# WE_1100_top.net
KiCad netlist of a schematic drawn in Altium Designer
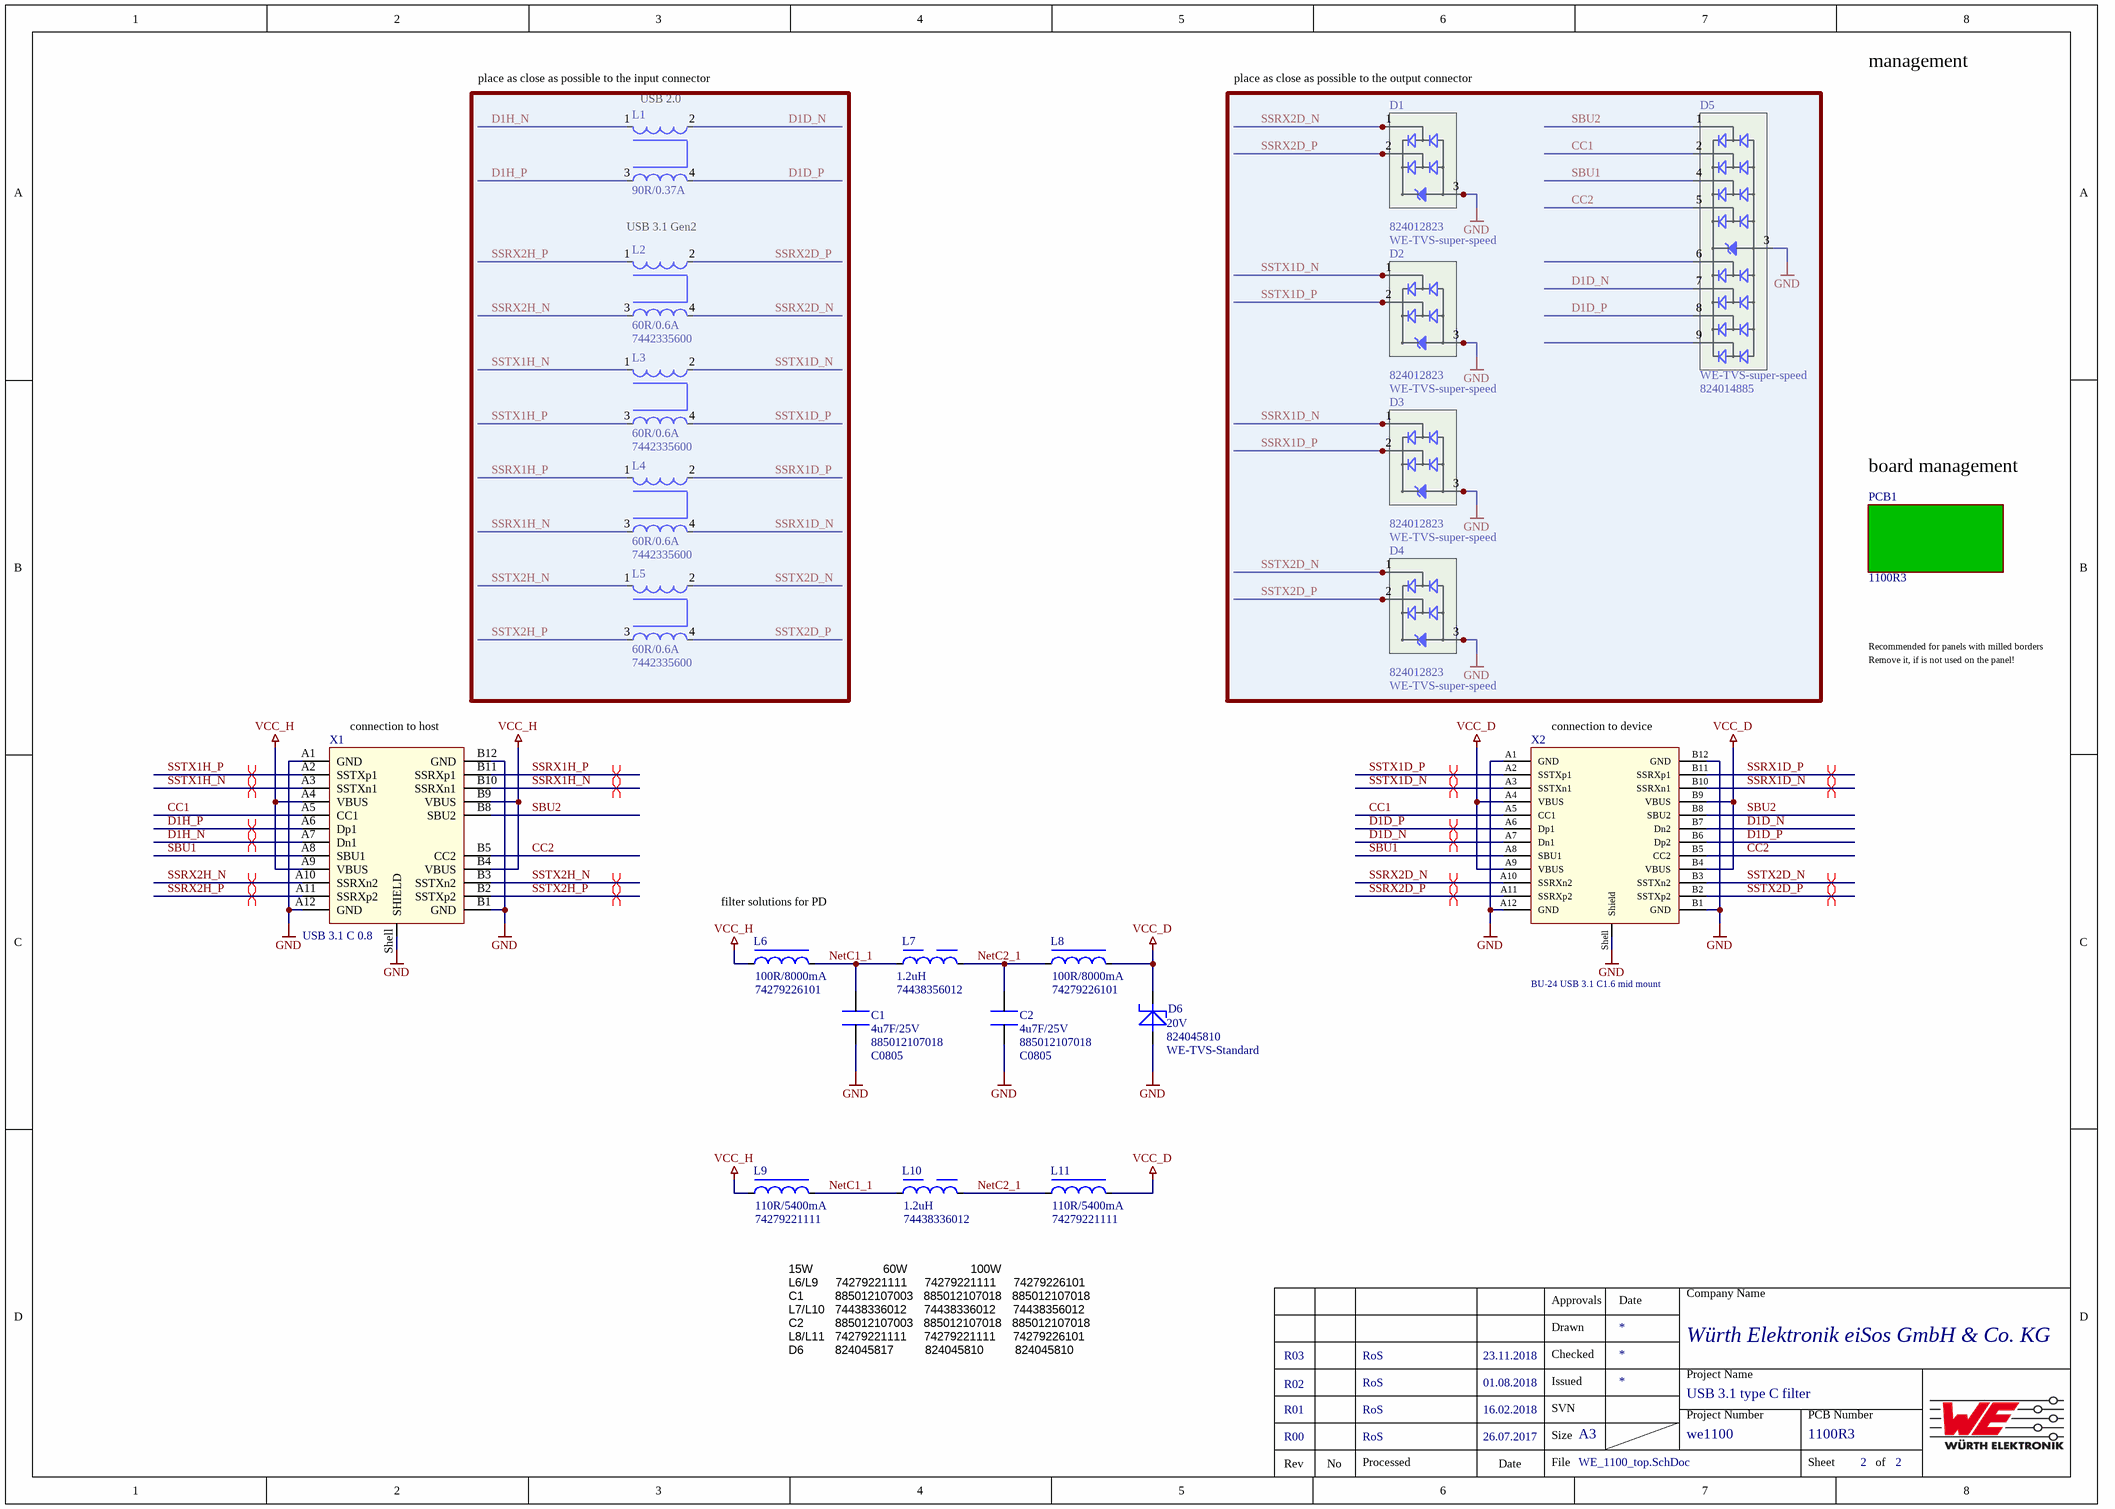
[diagram p0: WE_1100_top.SchDoc]

(export (version "E")
  (design (tool "Eeschema 10.0.6"))
  (components
    (comp (ref "C1")
      (value "4u7F/25V")
      (footprint "C0805 (reflow)")
      (description "Ceramic SMT X5R 4,7uF/25V 0805")
      (fields
        (field (name "ART.-CODE") "885012107018")
        (field (name "MANUFACTURER") "WE")
        (field (name "TOLERANCE") "20%")
        (field (name "CASE") "C0805")
      )
      (libsource (lib "capacitor") (part "4UF7/25-X5R-0805"))
    )
    (comp (ref "C2")
      (value "4u7F/25V")
      (footprint "C0805 (reflow)")
      (description "Ceramic SMT X5R 4,7uF/25V 0805")
      (fields
        (field (name "ART.-CODE") "885012107018")
        (field (name "MANUFACTURER") "WE")
        (field (name "TOLERANCE") "20%")
        (field (name "CASE") "C0805")
      )
      (libsource (lib "capacitor") (part "4UF7/25-X5R-0805"))
    )
    (comp (ref "D1")
      (value "WE-TVS-super-speed")
      (footprint "DFN88P100X50-6L")
      (description "TVS, diode, array, 2 channel ESD protection, 3.3V, DFN1012-6")
      (fields
        (field (name "MANUFACTURER") "WE")
        (field (name "VOLTAGE") "3.3V")
        (field (name "PART-NO.") "824012823")
      )
      (libsource (lib "rectifier") (part "WE-TVS-ULC-DFN1012-6"))
    )
    (comp (ref "D2")
      (value "WE-TVS-super-speed")
      (footprint "DFN88P100X50-6L")
      (description "TVS, diode, array, 2 channel ESD protection, 3.3V, DFN1012-6")
      (fields
        (field (name "MANUFACTURER") "WE")
        (field (name "VOLTAGE") "3.3V")
        (field (name "PART-NO.") "824012823")
      )
      (libsource (lib "rectifier") (part "WE-TVS-ULC-DFN1012-6"))
    )
    (comp (ref "D3")
      (value "WE-TVS-super-speed")
      (footprint "DFN88P100X50-6L")
      (description "TVS, diode, array, 2 channel ESD protection, 3.3V, DFN1012-6")
      (fields
        (field (name "MANUFACTURER") "WE")
        (field (name "VOLTAGE") "3.3V")
        (field (name "PART-NO.") "824012823")
      )
      (libsource (lib "rectifier") (part "WE-TVS-ULC-DFN1012-6"))
    )
    (comp (ref "D4")
      (value "WE-TVS-super-speed")
      (footprint "DFN88P100X50-6L")
      (description "TVS, diode, array, 2 channel ESD protection, 3.3V, DFN1012-6")
      (fields
        (field (name "MANUFACTURER") "WE")
        (field (name "VOLTAGE") "3.3V")
        (field (name "PART-NO.") "824012823")
      )
      (libsource (lib "rectifier") (part "WE-TVS-ULC-DFN1012-6"))
    )
    (comp (ref "D5")
      (value "WE-TVS-super-speed")
      (footprint "DFN90P380X55-9L")
      (description "TVS, diode, array, 8 channel ESD protection, 1.2V, DFN3810-9")
      (fields
        (field (name "MANUFACTURER") "WE")
        (field (name "VOLTAGE") "1.2V")
        (field (name "PART-NO.") "824014885")
      )
      (libsource (lib "rectifier") (part "WE-TVS-ULC-DFN3810"))
    )
    (comp (ref "D6")
      (value "WE-TVS-Standard")
      (footprint "DFN110P160X55-2L")
      (description "TVS, diode, unidir, ESD protection, 20V, DFN1610")
      (fields
        (field (name "MANUFACTURER") "WE")
        (field (name "VOLTAGE") "20V")
        (field (name "PART-NO.") "824045810")
      )
      (libsource (lib "rectifier") (part "WE-TVS20-ULC-DFN1610"))
    )
    (comp (ref "L1")
      (value "90R/0.37A")
      (footprint "WE-CNSW-0805 (REFLOW)")
      (description "Common mode line filter SMD WE-CNSW (USB, LVDS)")
      (fields
        (field (name "MANUFACTURER") "WE")
        (field (name "TOLERANCE") "25%")
        (field (name "HELPURL") "d:\\Hardware\\Datasheet\\Induktivitäten\\WE-CNSW\\744231091.pdf")
      )
      (libsource (lib "inductance") (part "Z90R-370mA-WE-CNSW"))
    )
    (comp (ref "L2")
      (value "60R/0.6A")
      (footprint "WE-CNSW-HF-0504 (REFLOW)")
      (description "Common mode line filter SMD WE-CNSW HF (USB3.0)")
      (fields
        (field (name "MANUFACTURER") "WE")
        (field (name "TOLERANCE") "25%")
        (field (name "PART-NO.") "7442335600")
        (field (name "HELPURL") "d:\\Hardware\\Datasheet\\Induktivitäten\\WE-CNSW_HF\\7442335600.pdf")
      )
      (libsource (lib "inductance") (part "Z60R-600mA-WE-CNSW HF"))
    )
    (comp (ref "L3")
      (value "60R/0.6A")
      (footprint "WE-CNSW-HF-0504 (REFLOW)")
      (description "Common mode line filter SMD WE-CNSW HF (USB3.0)")
      (fields
        (field (name "MANUFACTURER") "WE")
        (field (name "TOLERANCE") "25%")
        (field (name "PART-NO.") "7442335600")
        (field (name "HELPURL") "d:\\Hardware\\Datasheet\\Induktivitäten\\WE-CNSW_HF\\7442335600.pdf")
      )
      (libsource (lib "inductance") (part "Z60R-600mA-WE-CNSW HF"))
    )
    (comp (ref "L4")
      (value "60R/0.6A")
      (footprint "WE-CNSW-HF-0504 (REFLOW)")
      (description "Common mode line filter SMD WE-CNSW HF (USB3.0)")
      (fields
        (field (name "MANUFACTURER") "WE")
        (field (name "TOLERANCE") "25%")
        (field (name "PART-NO.") "7442335600")
        (field (name "HELPURL") "d:\\Hardware\\Datasheet\\Induktivitäten\\WE-CNSW_HF\\7442335600.pdf")
      )
      (libsource (lib "inductance") (part "Z60R-600mA-WE-CNSW HF"))
    )
    (comp (ref "L5")
      (value "60R/0.6A")
      (footprint "WE-CNSW-HF-0504 (REFLOW)")
      (description "Common mode line filter SMD WE-CNSW HF (USB3.0)")
      (fields
        (field (name "MANUFACTURER") "WE")
        (field (name "TOLERANCE") "25%")
        (field (name "PART-NO.") "7442335600")
        (field (name "HELPURL") "d:\\Hardware\\Datasheet\\Induktivitäten\\WE-CNSW_HF\\7442335600.pdf")
      )
      (libsource (lib "inductance") (part "Z60R-600mA-WE-CNSW HF"))
    )
    (comp (ref "L6")
      (value "100R/8000mA")
      (footprint "WE-MPSB_1812")
      (description "Multilayer Power Suppression Bead 1812 100R at 100MHz/0.006R")
      (fields
        (field (name "ART.-CODE") "74279226101")
        (field (name "MANUFACTURER") "WE")
        (field (name "TOLERANCE") "25%")
        (field (name "HELPURL") "d:\\Hardware\\Datasheet\\Induktivitäten\\Ferrit\\74279226101.pdf")
      )
      (libsource (lib "inductance") (part "Z100R_8000mA_1812_MPSB"))
    )
    (comp (ref "L7")
      (value "1.2uH")
      (footprint "WE-MAPI_4020")
      (description "Inductor SMT WE-MAPI 4020 1.2uH/5800mA")
      (fields
        (field (name "MANUFACTURER") "WE")
        (field (name "ART.-CODE") "74438356012")
        (field (name "TOLERANCE") "20%")
        (field (name "HELPURL") "d:\\Hardware\\Datasheet\\Induktivitäten\\WE-MAPI\\74438356012.pdf")
      )
      (libsource (lib "inductance") (part "1UH2-5.8A-SMD-WE-MAPI 4020"))
    )
    (comp (ref "L8")
      (value "100R/8000mA")
      (footprint "WE-MPSB_1812")
      (description "Multilayer Power Suppression Bead 1812 100R at 100MHz/0.006R")
      (fields
        (field (name "ART.-CODE") "74279226101")
        (field (name "MANUFACTURER") "WE")
        (field (name "TOLERANCE") "25%")
        (field (name "HELPURL") "d:\\Hardware\\Datasheet\\Induktivitäten\\Ferrit\\74279226101.pdf")
      )
      (libsource (lib "inductance") (part "Z100R_8000mA_1812_MPSB"))
    )
    (comp (ref "L9")
      (value "110R/5400mA")
      (footprint "WE-MPSB_1206")
      (description "Multilayer Power Suppression Bead 1206 110R at 100MHz/0.0095R")
      (fields
        (field (name "ART.-CODE") "74279221111")
        (field (name "MANUFACTURER") "WE")
        (field (name "TOLERANCE") "25%")
        (field (name "HELPURL") "d:\\Hardware\\Datasheet\\Induktivitäten\\Ferrit\\74279221111.pdf")
      )
      (libsource (lib "inductance") (part "Z110R_5400mA_1206_MPSB"))
    )
    (comp (ref "L10")
      (value "1.2uH")
      (footprint "WE-MAPI_3020")
      (description "Inductor SMT WE-MAPI 3020 1.2uH/3900mA")
      (fields
        (field (name "MANUFACTURER") "WE")
        (field (name "ART.-CODE") "74438336012")
        (field (name "TOLERANCE") "20%")
        (field (name "HELPURL") "d:\\Hardware\\Datasheet\\Induktivitäten\\WE-MAPI\\74438336012.pdf")
      )
      (libsource (lib "inductance") (part "1UH2-3.9A-SMD-WE-MAPI 3020"))
    )
    (comp (ref "L11")
      (value "110R/5400mA")
      (footprint "WE-MPSB_1206")
      (description "Multilayer Power Suppression Bead 1206 110R at 100MHz/0.0095R")
      (fields
        (field (name "ART.-CODE") "74279221111")
        (field (name "MANUFACTURER") "WE")
        (field (name "TOLERANCE") "25%")
        (field (name "HELPURL") "d:\\Hardware\\Datasheet\\Induktivitäten\\Ferrit\\74279221111.pdf")
      )
      (libsource (lib "inductance") (part "Z110R_5400mA_1206_MPSB"))
    )
    (comp (ref "PCB1")
      (value "1100R3")
      (description "only for partlist")
      (libsource (lib "misc") (part "PCB"))
    )
    (comp (ref "X1")
      (value "USB 3.1 C 0.8")
      (footprint "632712000011")
      (description "male USB 3.1 Type C 24 pins 90° THT & SMT LP 0.8")
      (fields (field (name "MANUFACTURER") "WE") (field (name "VOLTAGE") "20V"))
      (libsource (lib "connector") (part "ST-24 USB 3.1 C 0.8"))
    )
    (comp (ref "X2")
      (value "BU-24 USB 3.1 C1.6 mid mount")
      (footprint "632723130112")
      (description "USB 3.1 Type C Receptacle WR-COM, Horizontal, THR / SMT")
      (fields (field (name "MANUFACTURER") "WE") (field (name "VOLTAGE") "20V"))
      (libsource (lib "connector") (part "BU-24 USB 3.1 C1.6 mid mount"))
    )
  )
  (nets
    (net (code "1") (name "/CC1") (class "Default")
      (node (ref "D5") (pin "2") (pinfunction "I/O2_2") (pintype "passive"))
      (node (ref "X1") (pin "A5") (pinfunction "CC1_A5") (pintype "passive"))
      (node (ref "X2") (pin "A5") (pinfunction "CC1_A5") (pintype "passive"))
    )
    (net (code "2") (name "/CC2") (class "Default")
      (node (ref "D5") (pin "5") (pinfunction "I/O4_5") (pintype "passive"))
      (node (ref "X1") (pin "B5") (pinfunction "CC2_B5") (pintype "passive"))
      (node (ref "X2") (pin "B5") (pinfunction "CC2_B5") (pintype "passive"))
    )
    (net (code "3") (name "/D1D_N") (class "Default")
      (node (ref "D5") (pin "7") (pinfunction "NC_7") (pintype "passive"))
      (node (ref "L1") (pin "2") (pintype "passive"))
      (node (ref "X2") (pin "A7") (pinfunction "Dn1_A7") (pintype "passive"))
      (node (ref "X2") (pin "B7") (pinfunction "Dn2_B7") (pintype "passive"))
    )
    (net (code "4") (name "/D1D_P") (class "Default")
      (node (ref "D5") (pin "8") (pinfunction "GND_8") (pintype "passive"))
      (node (ref "L1") (pin "4") (pintype "passive"))
      (node (ref "X2") (pin "A6") (pinfunction "Dp1_A6") (pintype "passive"))
      (node (ref "X2") (pin "B6") (pinfunction "Dp2_B6") (pintype "passive"))
    )
    (net (code "5") (name "/D1H_N") (class "Default")
      (node (ref "L1") (pin "1") (pintype "passive"))
      (node (ref "X1") (pin "A7") (pinfunction "Dn1_A7") (pintype "passive"))
    )
    (net (code "6") (name "/D1H_P") (class "Default")
      (node (ref "L1") (pin "3") (pintype "passive"))
      (node (ref "X1") (pin "A6") (pinfunction "Dp1_A6") (pintype "passive"))
    )
    (net (code "7") (name "/NetC1_1") (class "Default")
      (node (ref "C1") (pin "1") (pintype "passive"))
      (node (ref "L10") (pin "1") (pintype "passive"))
      (node (ref "L6") (pin "2") (pintype "passive"))
      (node (ref "L7") (pin "1") (pintype "passive"))
      (node (ref "L9") (pin "2") (pintype "passive"))
    )
    (net (code "8") (name "/NetC2_1") (class "Default")
      (node (ref "C2") (pin "1") (pintype "passive"))
      (node (ref "L10") (pin "2") (pintype "passive"))
      (node (ref "L11") (pin "1") (pintype "passive"))
      (node (ref "L7") (pin "2") (pintype "passive"))
      (node (ref "L8") (pin "1") (pintype "passive"))
    )
    (net (code "9") (name "/SBU1") (class "Default")
      (node (ref "D5") (pin "4") (pinfunction "I/O3_4") (pintype "passive"))
      (node (ref "X1") (pin "A8") (pinfunction "SBU1_A8") (pintype "passive"))
      (node (ref "X2") (pin "A8") (pinfunction "SBU1_A8") (pintype "passive"))
    )
    (net (code "10") (name "/SBU2") (class "Default")
      (node (ref "D5") (pin "1") (pinfunction "I/O1_1") (pintype "passive"))
      (node (ref "X1") (pin "B8") (pinfunction "SBU2_B8") (pintype "passive"))
      (node (ref "X2") (pin "B8") (pinfunction "SBU2_B8") (pintype "passive"))
    )
    (net (code "11") (name "/SSRX1D_N") (class "Default")
      (node (ref "D3") (pin "1") (pinfunction "I/O1_1") (pintype "passive"))
      (node (ref "D3") (pin "6") (pinfunction "I/O1_6") (pintype "passive"))
      (node (ref "L4") (pin "4") (pintype "passive"))
      (node (ref "X2") (pin "B10") (pinfunction "SSRXn1_B10") (pintype "passive"))
    )
    (net (code "12") (name "/SSRX1D_P") (class "Default")
      (node (ref "D3") (pin "2") (pinfunction "I/O2_2") (pintype "passive"))
      (node (ref "D3") (pin "5") (pinfunction "I/O2_5") (pintype "passive"))
      (node (ref "L4") (pin "2") (pintype "passive"))
      (node (ref "X2") (pin "B11") (pinfunction "SSRXp1_B11") (pintype "passive"))
    )
    (net (code "13") (name "/SSRX1H_N") (class "Default")
      (node (ref "L4") (pin "3") (pintype "passive"))
      (node (ref "X1") (pin "B10") (pinfunction "SSRXn1_B10") (pintype "passive"))
    )
    (net (code "14") (name "/SSRX1H_P") (class "Default")
      (node (ref "L4") (pin "1") (pintype "passive"))
      (node (ref "X1") (pin "B11") (pinfunction "SSRXp1_B11") (pintype "passive"))
    )
    (net (code "15") (name "/SSRX2D_N") (class "Default")
      (node (ref "D1") (pin "1") (pinfunction "I/O1_1") (pintype "passive"))
      (node (ref "D1") (pin "6") (pinfunction "I/O1_6") (pintype "passive"))
      (node (ref "L2") (pin "4") (pintype "passive"))
      (node (ref "X2") (pin "A10") (pinfunction "SSRXn2_A10") (pintype "passive"))
    )
    (net (code "16") (name "/SSRX2D_P") (class "Default")
      (node (ref "D1") (pin "2") (pinfunction "I/O2_2") (pintype "passive"))
      (node (ref "D1") (pin "5") (pinfunction "I/O2_5") (pintype "passive"))
      (node (ref "L2") (pin "2") (pintype "passive"))
      (node (ref "X2") (pin "A11") (pinfunction "SSRXp2_A11") (pintype "passive"))
    )
    (net (code "17") (name "/SSRX2H_N") (class "Default")
      (node (ref "L2") (pin "3") (pintype "passive"))
      (node (ref "X1") (pin "A10") (pinfunction "SSRXn2_A10") (pintype "passive"))
    )
    (net (code "18") (name "/SSRX2H_P") (class "Default")
      (node (ref "L2") (pin "1") (pintype "passive"))
      (node (ref "X1") (pin "A11") (pinfunction "SSRXp2_A11") (pintype "passive"))
    )
    (net (code "19") (name "/SSTX1D_N") (class "Default")
      (node (ref "D2") (pin "1") (pinfunction "I/O1_1") (pintype "passive"))
      (node (ref "D2") (pin "6") (pinfunction "I/O1_6") (pintype "passive"))
      (node (ref "L3") (pin "2") (pintype "passive"))
      (node (ref "X2") (pin "A3") (pinfunction "SSTXn1_A3") (pintype "passive"))
    )
    (net (code "20") (name "/SSTX1D_P") (class "Default")
      (node (ref "D2") (pin "2") (pinfunction "I/O2_2") (pintype "passive"))
      (node (ref "D2") (pin "5") (pinfunction "I/O2_5") (pintype "passive"))
      (node (ref "L3") (pin "4") (pintype "passive"))
      (node (ref "X2") (pin "A2") (pinfunction "SSTXp1_A2") (pintype "passive"))
    )
    (net (code "21") (name "/SSTX1H_N") (class "Default")
      (node (ref "L3") (pin "1") (pintype "passive"))
      (node (ref "X1") (pin "A3") (pinfunction "SSTXn1_A3") (pintype "passive"))
    )
    (net (code "22") (name "/SSTX1H_P") (class "Default")
      (node (ref "L3") (pin "3") (pintype "passive"))
      (node (ref "X1") (pin "A2") (pinfunction "SSTXp1_A2") (pintype "passive"))
    )
    (net (code "23") (name "/SSTX2D_N") (class "Default")
      (node (ref "D4") (pin "1") (pinfunction "I/O1_1") (pintype "passive"))
      (node (ref "D4") (pin "6") (pinfunction "I/O1_6") (pintype "passive"))
      (node (ref "L5") (pin "2") (pintype "passive"))
      (node (ref "X2") (pin "B3") (pinfunction "SSTXn2_B3") (pintype "passive"))
    )
    (net (code "24") (name "/SSTX2D_P") (class "Default")
      (node (ref "D4") (pin "2") (pinfunction "I/O2_2") (pintype "passive"))
      (node (ref "D4") (pin "5") (pinfunction "I/O2_5") (pintype "passive"))
      (node (ref "L5") (pin "4") (pintype "passive"))
      (node (ref "X2") (pin "B2") (pinfunction "SSTXp2_B2") (pintype "passive"))
    )
    (net (code "25") (name "/SSTX2H_N") (class "Default")
      (node (ref "L5") (pin "1") (pintype "passive"))
      (node (ref "X1") (pin "B3") (pinfunction "SSTXn2_B3") (pintype "passive"))
    )
    (net (code "26") (name "/SSTX2H_P") (class "Default")
      (node (ref "L5") (pin "3") (pintype "passive"))
      (node (ref "X1") (pin "B2") (pinfunction "SSTXp2_B2") (pintype "passive"))
    )
    (net (code "27") (name "GND") (class "Default")
      (node (ref "C1") (pin "2") (pintype "passive"))
      (node (ref "C2") (pin "2") (pintype "passive"))
      (node (ref "D1") (pin "3") (pinfunction "VDD_3") (pintype "passive"))
      (node (ref "D1") (pin "4") (pinfunction "VDD_4") (pintype "passive"))
      (node (ref "D2") (pin "3") (pinfunction "VDD_3") (pintype "passive"))
      (node (ref "D2") (pin "4") (pinfunction "VDD_4") (pintype "passive"))
      (node (ref "D3") (pin "3") (pinfunction "VDD_3") (pintype "passive"))
      (node (ref "D3") (pin "4") (pinfunction "VDD_4") (pintype "passive"))
      (node (ref "D4") (pin "3") (pinfunction "VDD_3") (pintype "passive"))
      (node (ref "D4") (pin "4") (pinfunction "VDD_4") (pintype "passive"))
      (node (ref "D5") (pin "3") (pinfunction "VDD_3") (pintype "passive"))
      (node (ref "D6") (pin "2") (pinfunction "I/O2_2") (pintype "passive"))
      (node (ref "X1") (pin "A1") (pinfunction "GND_A1") (pintype "passive"))
      (node (ref "X1") (pin "A12") (pinfunction "GND_A12") (pintype "passive"))
      (node (ref "X1") (pin "B1") (pinfunction "GND_B1") (pintype "passive"))
      (node (ref "X1") (pin "B12") (pinfunction "GND_B12") (pintype "passive"))
      (node (ref "X1") (pin "Shell") (pinfunction "SHIELD_Shell") (pintype "passive"))
      (node (ref "X2") (pin "A1") (pinfunction "GND_A1") (pintype "passive"))
      (node (ref "X2") (pin "A12") (pinfunction "GND_A12") (pintype "passive"))
      (node (ref "X2") (pin "B1") (pinfunction "GND_B1") (pintype "passive"))
      (node (ref "X2") (pin "B12") (pinfunction "GND_B12") (pintype "passive"))
      (node (ref "X2") (pin "Shell") (pinfunction "Shield_Shell") (pintype "passive"))
    )
    (net (code "28") (name "VCC_D") (class "Default")
      (node (ref "D6") (pin "1") (pinfunction "I/O1_1") (pintype "passive"))
      (node (ref "L11") (pin "2") (pintype "passive"))
      (node (ref "L8") (pin "2") (pintype "passive"))
      (node (ref "X2") (pin "A4") (pinfunction "VBUS_A4") (pintype "passive"))
      (node (ref "X2") (pin "A9") (pinfunction "VBUS_A9") (pintype "passive"))
      (node (ref "X2") (pin "B4") (pinfunction "VBUS_B4") (pintype "passive"))
      (node (ref "X2") (pin "B9") (pinfunction "VBUS_B9") (pintype "passive"))
    )
    (net (code "29") (name "VCC_H") (class "Default")
      (node (ref "L6") (pin "1") (pintype "passive"))
      (node (ref "L9") (pin "1") (pintype "passive"))
      (node (ref "X1") (pin "A4") (pinfunction "VBUS_A4") (pintype "passive"))
      (node (ref "X1") (pin "A9") (pinfunction "VBUS_A9") (pintype "passive"))
      (node (ref "X1") (pin "B4") (pinfunction "VBUS_B4") (pintype "passive"))
      (node (ref "X1") (pin "B9") (pinfunction "VBUS_B9") (pintype "passive"))
    )
    (net (code "30") (name "unconnected-(D5-NC-Pad6)") (class "Default")
      (node (ref "D5") (pin "6") (pinfunction "NC_6") (pintype "passive"))
    )
    (net (code "31") (name "unconnected-(D5-NC-Pad9)") (class "Default")
      (node (ref "D5") (pin "9") (pinfunction "NC_9") (pintype "passive"))
    )
  )
)
